# Sheet2.net
KiCad netlist of a schematic drawn in Altium Designer
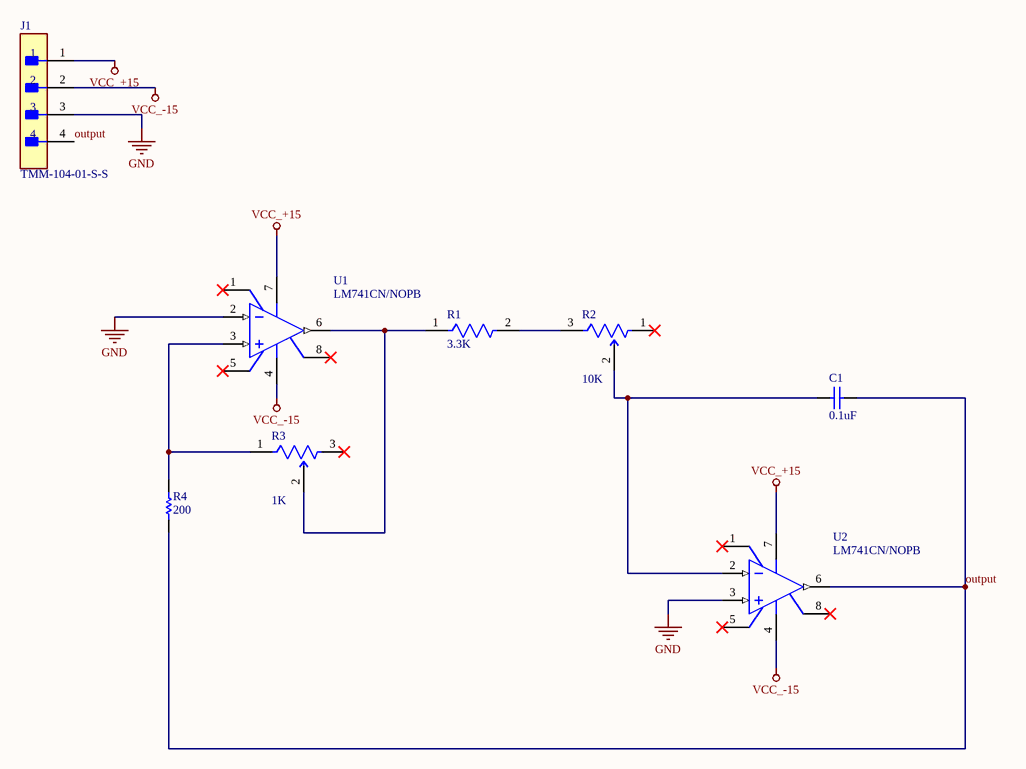
[diagram p0: Sheet2.SchDoc]

(export (version "E")
  (design (tool "Eeschema 10.0.6"))
  (components
    (comp (ref "C1")
      (value "0.1uF")
      (footprint "CAPC2013X94X50LL20T25")
      (fields
        (field (name "MANUFACTURER") "AVX Interconnect / Elco")
        (field (name "PART NUMBER") "08051C104KAZ2A")
      )
      (libsource (lib "Altium Content Vault") (part "CAP"))
    )
    (comp (ref "J1")
      (value "TMM-104-01-S-S")
      (footprint "FP-TMM-104-01-S-S-MFG")
      (description "CONN HEADER VERT 4POS 2MM")
      (libsource (lib "Altium Content Vault") (part "299a8cea1bdcbc3624fe62c390fa72c"))
    )
    (comp (ref "R1")
      (value "3.3K")
      (footprint "FP-CRCW1206-e3-MFG")
      (description "RES Thick Film, 3.3kΩ, 1%, 0.25W, 100ppm/°C, 1206")
      (fields (field (name "TOLERANCE") "1%"))
      (libsource (lib "Altium Content Vault") (part "1029c3af85768c4190bb7ad29bc67b5"))
    )
    (comp (ref "R2")
      (value "10K")
      (footprint "FP-3310R-MFG")
      (description "POT 10K OHM 1/4W PLASTIC LINEAR")
      (fields (field (name "TOLERANCE") "20%"))
      (libsource (lib "Altium Content Vault") (part "cfaf082cc24db979c98760cc608bf4a"))
    )
    (comp (ref "R3")
      (value "1K")
      (footprint "FP-83A1A-B28-J10L-MFG")
      (description "POT 1K OHM 1W WIREWOUND LINEAR")
      (fields (field (name "TOLERANCE") "5%"))
      (libsource (lib "Altium Content Vault") (part "2dcfd2547301a7d3209a5e99acfd772"))
    )
    (comp (ref "R4")
      (value "200")
      (footprint "RESC3216X70X40LL20T20")
      (fields (field (name "MANUFACTURER") "KOA Speer") (field (name "PART NUMBER") "RK73B2BTTD201J"))
      (libsource (lib "Altium Content Vault") (part "RES"))
    )
    (comp (ref "U1")
      (value "LM741CN/NOPB")
      (footprint "P0008A")
      (description "Operational Amplifier, 8-pin MDIP, Pb-Free")
      (fields (field (name "MANUFACTURER") "Texas Instruments"))
      (libsource (lib "Altium Content Vault") (part "AMP-OPA-LM741-8"))
    )
    (comp (ref "U2")
      (value "LM741CN/NOPB")
      (footprint "P0008A")
      (description "Operational Amplifier, 8-pin MDIP, Pb-Free")
      (fields (field (name "MANUFACTURER") "Texas Instruments"))
      (libsource (lib "Altium Content Vault") (part "AMP-OPA-LM741-8"))
    )
  )
  (nets
    (net (code "1") (name "/output") (class "Default")
      (node (ref "C1") (pin "2") (pinfunction "2_2") (pintype "passive"))
      (node (ref "J1") (pin "4") (pinfunction "4_4") (pintype "passive"))
      (node (ref "R4") (pin "1") (pinfunction "1_1") (pintype "passive"))
      (node (ref "U2") (pin "6") (pinfunction "OUT_6") (pintype "output"))
    )
    (net (code "2") (name "GND") (class "Default")
      (node (ref "J1") (pin "3") (pinfunction "3_3") (pintype "passive"))
      (node (ref "U1") (pin "2") (pinfunction "IN-_2") (pintype "input"))
      (node (ref "U2") (pin "3") (pinfunction "IN+_3") (pintype "input"))
    )
    (net (code "3") (name "Net-(R2-CW)") (class "Default")
      (node (ref "R1") (pin "2") (pinfunction "2_2") (pintype "passive"))
      (node (ref "R2") (pin "3") (pinfunction "CW_3") (pintype "passive"))
    )
    (net (code "4") (name "Net-(R3-CCW)") (class "Default")
      (node (ref "R3") (pin "1") (pinfunction "CCW_1") (pintype "passive"))
      (node (ref "R4") (pin "2") (pinfunction "2_2") (pintype "passive"))
      (node (ref "U1") (pin "3") (pinfunction "IN+_3") (pintype "input"))
    )
    (net (code "5") (name "Net-(R3-WIPER)") (class "Default")
      (node (ref "R1") (pin "1") (pinfunction "1_1") (pintype "passive"))
      (node (ref "R3") (pin "2") (pinfunction "WIPER_2") (pintype "passive"))
      (node (ref "U1") (pin "6") (pinfunction "OUT_6") (pintype "output"))
    )
    (net (code "6") (name "Net-(U2-IN-)") (class "Default")
      (node (ref "C1") (pin "1") (pinfunction "1_1") (pintype "passive"))
      (node (ref "R2") (pin "2") (pinfunction "2_2") (pintype "passive"))
      (node (ref "U2") (pin "2") (pinfunction "IN-_2") (pintype "input"))
    )
    (net (code "7") (name "VCC_+15") (class "Default")
      (node (ref "J1") (pin "1") (pinfunction "1_1") (pintype "passive"))
      (node (ref "U1") (pin "7") (pinfunction "V+_7") (pintype "power_in"))
      (node (ref "U2") (pin "7") (pinfunction "V+_7") (pintype "power_in"))
    )
    (net (code "8") (name "VCC_-15") (class "Default")
      (node (ref "J1") (pin "2") (pinfunction "2_2") (pintype "passive"))
      (node (ref "U1") (pin "4") (pinfunction "V-_4") (pintype "power_in"))
      (node (ref "U2") (pin "4") (pinfunction "V-_4") (pintype "power_in"))
    )
    (net (code "9") (name "unconnected-(R2-CCW-Pad1)") (class "Default")
      (node (ref "R2") (pin "1") (pinfunction "CCW_1") (pintype "passive+no_connect"))
    )
    (net (code "10") (name "unconnected-(R3-CW-Pad3)") (class "Default")
      (node (ref "R3") (pin "3") (pinfunction "CW_3") (pintype "passive+no_connect"))
    )
    (net (code "11") (name "unconnected-(U1-NC-Pad8)") (class "Default")
      (node (ref "U1") (pin "8") (pinfunction "NC_8") (pintype "passive+no_connect"))
    )
    (net (code "12") (name "unconnected-(U1-OFS_NULL-Pad1)") (class "Default")
      (node (ref "U1") (pin "1") (pinfunction "OFS_NULL_1") (pintype "passive+no_connect"))
    )
    (net (code "13") (name "unconnected-(U1-OFS_NULL-Pad5)") (class "Default")
      (node (ref "U1") (pin "5") (pinfunction "OFS_NULL_5") (pintype "passive+no_connect"))
    )
    (net (code "14") (name "unconnected-(U2-NC-Pad8)") (class "Default")
      (node (ref "U2") (pin "8") (pinfunction "NC_8") (pintype "passive+no_connect"))
    )
    (net (code "15") (name "unconnected-(U2-OFS_NULL-Pad1)") (class "Default")
      (node (ref "U2") (pin "1") (pinfunction "OFS_NULL_1") (pintype "passive+no_connect"))
    )
    (net (code "16") (name "unconnected-(U2-OFS_NULL-Pad5)") (class "Default")
      (node (ref "U2") (pin "5") (pinfunction "OFS_NULL_5") (pintype "passive+no_connect"))
    )
  )
)
